# multi-pcb-analog-with-cc.net
KiCad netlist of a schematic drawn in EAGLE
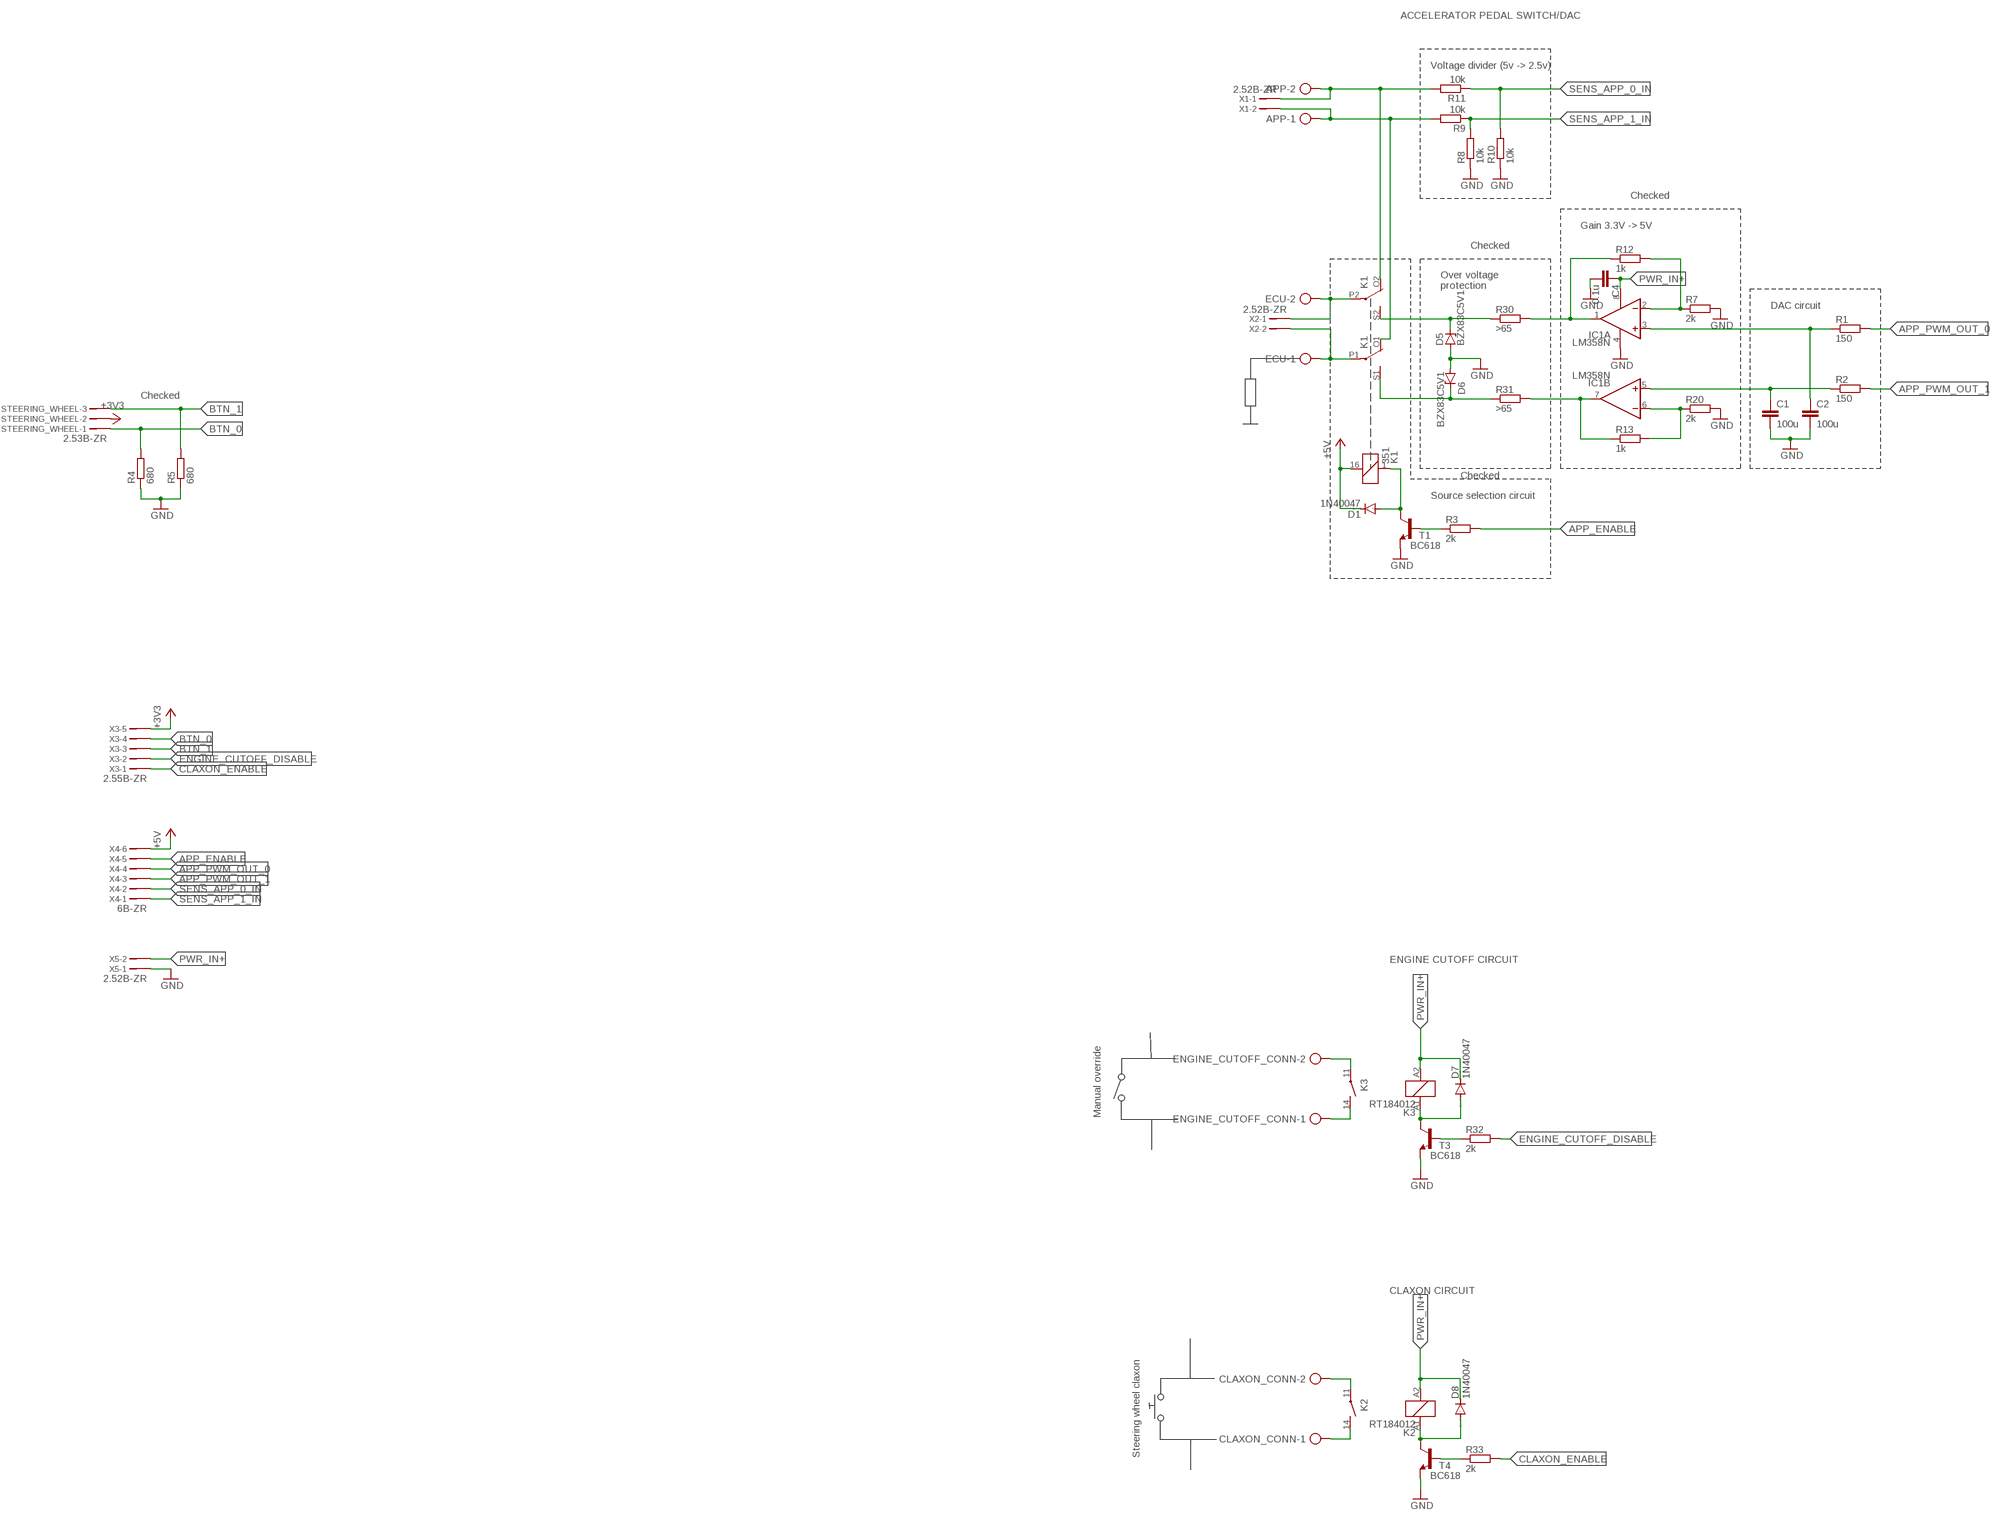
[diagram p0: schematic, sheet 1]

(export (version "E")
  (design (tool "Eeschema 10.0.6"))
  (components
    (comp (ref "APP")
      (value "AK300/2")
      (footprint "eagle-import:AK300_2")
      (libsource (lib "eagle-import") (part "AK300/2"))
    )
    (comp (ref "C1")
      (value "100u")
      (footprint "eagle-import:C025-050X050")
      (libsource (lib "eagle-import") (part "C-EU025-050X050"))
    )
    (comp (ref "C2")
      (value "100u")
      (footprint "eagle-import:C025-050X050")
      (libsource (lib "eagle-import") (part "C-EU025-050X050"))
    )
    (comp (ref "C4")
      (value "0.1u")
      (footprint "eagle-import:C025-050X050")
      (libsource (lib "eagle-import") (part "C-EU025-050X050"))
    )
    (comp (ref "CLAXON_CONN")
      (value "AK300/2")
      (footprint "eagle-import:AK300_2")
      (libsource (lib "eagle-import") (part "AK300/2"))
    )
    (comp (ref "D1")
      (value "1N40047")
      (footprint "eagle-import:DO41-7.6")
      (libsource (lib "eagle-import") (part "1N40047"))
    )
    (comp (ref "D5")
      (value "BZX83C5V1")
      (footprint "eagle-import:DO41Z7.6")
      (libsource (lib "eagle-import") (part "BZX857"))
    )
    (comp (ref "D6")
      (value "BZX83C5V1")
      (footprint "eagle-import:DO41Z7.6")
      (libsource (lib "eagle-import") (part "BZX857"))
    )
    (comp (ref "D7")
      (value "1N40047")
      (footprint "eagle-import:DO41-7.6")
      (libsource (lib "eagle-import") (part "1N40047"))
    )
    (comp (ref "D8")
      (value "1N40047")
      (footprint "eagle-import:DO41-7.6")
      (libsource (lib "eagle-import") (part "1N40047"))
    )
    (comp (ref "ECU")
      (value "AK300/2")
      (footprint "eagle-import:AK300_2")
      (libsource (lib "eagle-import") (part "AK300/2"))
    )
    (comp (ref "ENGINE_CUTOFF_CONN")
      (value "AK300/2")
      (footprint "eagle-import:AK300_2")
      (libsource (lib "eagle-import") (part "AK300/2"))
    )
    (comp (ref "IC1")
      (value "LM358N")
      (footprint "eagle-import:DIL08")
      (libsource (lib "eagle-import") (part "LM358N"))
    )
    (comp (ref "K1")
      (value "351")
      (footprint "eagle-import:351")
      (libsource (lib "eagle-import") (part "351"))
    )
    (comp (ref "K2")
      (value "RT184012")
      (footprint "eagle-import:RT-N_O12A3.5")
      (fields (field (name "MF") "TYCO ELECTRONICS"))
      (libsource (lib "eagle-import") (part "RT?184012"))
    )
    (comp (ref "K3")
      (value "RT184012")
      (footprint "eagle-import:RT-N_O12A3.5")
      (fields (field (name "MF") "TYCO ELECTRONICS"))
      (libsource (lib "eagle-import") (part "RT?184012"))
    )
    (comp (ref "R1")
      (value "150")
      (footprint "eagle-import:0207_7")
      (libsource (lib "eagle-import") (part "R-EU_0207/7"))
    )
    (comp (ref "R2")
      (value "150")
      (footprint "eagle-import:0207_7")
      (libsource (lib "eagle-import") (part "R-EU_0207/7"))
    )
    (comp (ref "R3")
      (value "2k")
      (footprint "eagle-import:0207_7")
      (libsource (lib "eagle-import") (part "R-EU_0207/7"))
    )
    (comp (ref "R4")
      (value "680")
      (footprint "eagle-import:0207_7")
      (libsource (lib "eagle-import") (part "R-EU_0207/7"))
    )
    (comp (ref "R5")
      (value "680")
      (footprint "eagle-import:0207_7")
      (libsource (lib "eagle-import") (part "R-EU_0207/7"))
    )
    (comp (ref "R7")
      (value "2k")
      (footprint "eagle-import:0207_7")
      (libsource (lib "eagle-import") (part "R-EU_0207/7"))
    )
    (comp (ref "R8")
      (value "10k")
      (footprint "eagle-import:0207_7")
      (libsource (lib "eagle-import") (part "R-EU_0207/7"))
    )
    (comp (ref "R9")
      (value "10k")
      (footprint "eagle-import:0207_7")
      (libsource (lib "eagle-import") (part "R-EU_0207/7"))
    )
    (comp (ref "R10")
      (value "10k")
      (footprint "eagle-import:0207_7")
      (libsource (lib "eagle-import") (part "R-EU_0207/7"))
    )
    (comp (ref "R11")
      (value "10k")
      (footprint "eagle-import:0207_7")
      (libsource (lib "eagle-import") (part "R-EU_0207/7"))
    )
    (comp (ref "R12")
      (value "1k")
      (footprint "eagle-import:0207_7")
      (libsource (lib "eagle-import") (part "R-EU_0207/7"))
    )
    (comp (ref "R13")
      (value "1k")
      (footprint "eagle-import:0207_7")
      (libsource (lib "eagle-import") (part "R-EU_0207/7"))
    )
    (comp (ref "R20")
      (value "2k")
      (footprint "eagle-import:0207_7")
      (libsource (lib "eagle-import") (part "R-EU_0207/7"))
    )
    (comp (ref "R30")
      (value ">65")
      (footprint "eagle-import:0207_7")
      (libsource (lib "eagle-import") (part "R-EU_0207/7"))
    )
    (comp (ref "R31")
      (value ">65")
      (footprint "eagle-import:0207_7")
      (libsource (lib "eagle-import") (part "R-EU_0207/7"))
    )
    (comp (ref "R32")
      (value "2k")
      (footprint "eagle-import:0207_7")
      (libsource (lib "eagle-import") (part "R-EU_0207/7"))
    )
    (comp (ref "R33")
      (value "2k")
      (footprint "eagle-import:0207_7")
      (libsource (lib "eagle-import") (part "R-EU_0207/7"))
    )
    (comp (ref "STEERING_WHEEL")
      (value "2.53B-ZR")
      (footprint "eagle-import:B3B-ZR2.5")
      (libsource (lib "eagle-import") (part "?3B-ZR2.5"))
    )
    (comp (ref "T1")
      (value "BC618")
      (footprint "eagle-import:TO92-EBC")
      (libsource (lib "eagle-import") (part "BC618"))
    )
    (comp (ref "T3")
      (value "BC618")
      (footprint "eagle-import:TO92-EBC")
      (libsource (lib "eagle-import") (part "BC618"))
    )
    (comp (ref "T4")
      (value "BC618")
      (footprint "eagle-import:TO92-EBC")
      (libsource (lib "eagle-import") (part "BC618"))
    )
    (comp (ref "X1")
      (value "2.52B-ZR")
      (footprint "eagle-import:B2B-ZR2.5")
      (libsource (lib "eagle-import") (part "?2B-ZR2.5"))
    )
    (comp (ref "X2")
      (value "2.52B-ZR")
      (footprint "eagle-import:B2B-ZR2.5")
      (libsource (lib "eagle-import") (part "?2B-ZR2.5"))
    )
    (comp (ref "X3")
      (value "2.55B-ZR")
      (footprint "eagle-import:B5B-ZR2.5")
      (libsource (lib "eagle-import") (part "?5B-ZR2.5"))
    )
    (comp (ref "X4")
      (value "6B-ZR")
      (footprint "eagle-import:B6B-ZR2.5")
      (libsource (lib "eagle-import") (part "?6B-ZR"))
    )
    (comp (ref "X5")
      (value "2.52B-ZR")
      (footprint "eagle-import:B2B-ZR2.5")
      (libsource (lib "eagle-import") (part "?2B-ZR2.5"))
    )
  )
  (nets
    (net (code "1") (name "+3V3") (class "Default")
      (node (ref "STEERING_WHEEL") (pin "2") (pinfunction "1_2") (pintype "passive"))
      (node (ref "X3") (pin "5") (pinfunction "1_5") (pintype "passive"))
    )
    (net (code "2") (name "+5V") (class "Default")
      (node (ref "D1") (pin "C") (pinfunction "C_C") (pintype "passive"))
      (node (ref "K1") (pin "16") (pinfunction "2_16") (pintype "passive"))
      (node (ref "X4") (pin "6") (pinfunction "1_6") (pintype "passive"))
    )
    (net (code "3") (name "APP_ENABLE") (class "Default")
      (node (ref "R3") (pin "2") (pinfunction "2_2") (pintype "passive"))
      (node (ref "X4") (pin "5") (pinfunction "1_5") (pintype "passive"))
    )
    (net (code "4") (name "APP_PWM_OUT_0") (class "Default")
      (node (ref "R1") (pin "2") (pinfunction "2_2") (pintype "passive"))
      (node (ref "X4") (pin "4") (pinfunction "1_4") (pintype "passive"))
    )
    (net (code "5") (name "APP_PWM_OUT_1") (class "Default")
      (node (ref "R2") (pin "2") (pinfunction "2_2") (pintype "passive"))
      (node (ref "X4") (pin "3") (pinfunction "1_3") (pintype "passive"))
    )
    (net (code "6") (name "BTN_0") (class "Default")
      (node (ref "R4") (pin "2") (pinfunction "2_2") (pintype "passive"))
      (node (ref "STEERING_WHEEL") (pin "1") (pinfunction "1_1") (pintype "passive"))
      (node (ref "X3") (pin "4") (pinfunction "1_4") (pintype "passive"))
    )
    (net (code "7") (name "BTN_1") (class "Default")
      (node (ref "R5") (pin "2") (pinfunction "2_2") (pintype "passive"))
      (node (ref "STEERING_WHEEL") (pin "3") (pinfunction "1_3") (pintype "passive"))
      (node (ref "X3") (pin "3") (pinfunction "1_3") (pintype "passive"))
    )
    (net (code "8") (name "CLAXON_ENABLE") (class "Default")
      (node (ref "R33") (pin "2") (pinfunction "2_2") (pintype "passive"))
      (node (ref "X3") (pin "1") (pinfunction "1_1") (pintype "passive"))
    )
    (net (code "9") (name "ENGINE_CUTOFF_DISABLE") (class "Default")
      (node (ref "R32") (pin "2") (pinfunction "2_2") (pintype "passive"))
      (node (ref "X3") (pin "2") (pinfunction "1_2") (pintype "passive"))
    )
    (net (code "10") (name "GND") (class "Default")
      (node (ref "C1") (pin "2") (pinfunction "2_2") (pintype "passive"))
      (node (ref "C2") (pin "2") (pinfunction "2_2") (pintype "passive"))
      (node (ref "C4") (pin "2") (pinfunction "2_2") (pintype "passive"))
      (node (ref "D5") (pin "A") (pinfunction "A_A") (pintype "passive"))
      (node (ref "D6") (pin "A") (pinfunction "A_A") (pintype "passive"))
      (node (ref "IC1") (pin "4") (pinfunction "V-_4") (pintype "power_in"))
      (node (ref "R10") (pin "1") (pinfunction "1_1") (pintype "passive"))
      (node (ref "R20") (pin "2") (pinfunction "2_2") (pintype "passive"))
      (node (ref "R4") (pin "1") (pinfunction "1_1") (pintype "passive"))
      (node (ref "R5") (pin "1") (pinfunction "1_1") (pintype "passive"))
      (node (ref "R7") (pin "2") (pinfunction "2_2") (pintype "passive"))
      (node (ref "R8") (pin "1") (pinfunction "1_1") (pintype "passive"))
      (node (ref "T1") (pin "E") (pinfunction "E_E") (pintype "passive"))
      (node (ref "T3") (pin "E") (pinfunction "E_E") (pintype "passive"))
      (node (ref "T4") (pin "E") (pinfunction "E_E") (pintype "passive"))
      (node (ref "X5") (pin "1") (pinfunction "1_1") (pintype "passive"))
    )
    (net (code "11") (name "Net-(APPA-KL)") (class "Default")
      (node (ref "APP") (pin "1") (pinfunction "KL_1") (pintype "passive"))
      (node (ref "K1") (pin "O1") (pinfunction "O_O1") (pintype "passive"))
      (node (ref "R9") (pin "2") (pinfunction "2_2") (pintype "passive"))
      (node (ref "X1") (pin "2") (pinfunction "1_2") (pintype "passive"))
    )
    (net (code "12") (name "Net-(APPB-KL)") (class "Default")
      (node (ref "APP") (pin "2") (pinfunction "KL_2") (pintype "passive"))
      (node (ref "K1") (pin "O2") (pinfunction "O_O2") (pintype "passive"))
      (node (ref "R11") (pin "2") (pinfunction "2_2") (pintype "passive"))
      (node (ref "X1") (pin "1") (pinfunction "1_1") (pintype "passive"))
    )
    (net (code "13") (name "Net-(CLAXON_CONNA-KL)") (class "Default")
      (node (ref "CLAXON_CONN") (pin "1") (pinfunction "KL_1") (pintype "passive"))
      (node (ref "K2") (pin "14") (pinfunction "S_14") (pintype "passive"))
    )
    (net (code "14") (name "Net-(CLAXON_CONNB-KL)") (class "Default")
      (node (ref "CLAXON_CONN") (pin "2") (pinfunction "KL_2") (pintype "passive"))
      (node (ref "K2") (pin "11") (pinfunction "P_11") (pintype "passive"))
    )
    (net (code "15") (name "Net-(D1-PadA)") (class "Default")
      (node (ref "D1") (pin "A") (pinfunction "A_A") (pintype "passive"))
      (node (ref "K1") (pin "1") (pinfunction "1_1") (pintype "passive"))
      (node (ref "T1") (pin "C") (pinfunction "C_C") (pintype "passive"))
    )
    (net (code "16") (name "Net-(ECUA-KL)") (class "Default")
      (node (ref "ECU") (pin "1") (pinfunction "KL_1") (pintype "passive"))
      (node (ref "K1") (pin "P1") (pinfunction "P_P1") (pintype "passive"))
      (node (ref "X2") (pin "2") (pinfunction "1_2") (pintype "passive"))
    )
    (net (code "17") (name "Net-(ECUB-KL)") (class "Default")
      (node (ref "ECU") (pin "2") (pinfunction "KL_2") (pintype "passive"))
      (node (ref "K1") (pin "P2") (pinfunction "P_P2") (pintype "passive"))
      (node (ref "X2") (pin "1") (pinfunction "1_1") (pintype "passive"))
    )
    (net (code "18") (name "Net-(ENGINE_CUTOFF_CONNA-KL)") (class "Default")
      (node (ref "ENGINE_CUTOFF_CONN") (pin "1") (pinfunction "KL_1") (pintype "passive"))
      (node (ref "K3") (pin "14") (pinfunction "S_14") (pintype "passive"))
    )
    (net (code "19") (name "Net-(ENGINE_CUTOFF_CONNB-KL)") (class "Default")
      (node (ref "ENGINE_CUTOFF_CONN") (pin "2") (pinfunction "KL_2") (pintype "passive"))
      (node (ref "K3") (pin "11") (pinfunction "P_11") (pintype "passive"))
    )
    (net (code "20") (name "Net-(IC1A-+IN)") (class "Default")
      (node (ref "C2") (pin "1") (pinfunction "1_1") (pintype "passive"))
      (node (ref "IC1") (pin "3") (pinfunction "+IN_3") (pintype "input"))
      (node (ref "R1") (pin "1") (pinfunction "1_1") (pintype "passive"))
    )
    (net (code "21") (name "Net-(IC1A--IN)") (class "Default")
      (node (ref "IC1") (pin "2") (pinfunction "-IN_2") (pintype "input"))
      (node (ref "R12") (pin "2") (pinfunction "2_2") (pintype "passive"))
      (node (ref "R7") (pin "1") (pinfunction "1_1") (pintype "passive"))
    )
    (net (code "22") (name "Net-(IC1A-OUT)") (class "Default")
      (node (ref "IC1") (pin "1") (pinfunction "OUT_1") (pintype "output"))
      (node (ref "R12") (pin "1") (pinfunction "1_1") (pintype "passive"))
      (node (ref "R30") (pin "2") (pinfunction "2_2") (pintype "passive"))
    )
    (net (code "23") (name "Net-(IC1B-+IN)") (class "Default")
      (node (ref "C1") (pin "1") (pinfunction "1_1") (pintype "passive"))
      (node (ref "IC1") (pin "5") (pinfunction "+IN_5") (pintype "input"))
      (node (ref "R2") (pin "1") (pinfunction "1_1") (pintype "passive"))
    )
    (net (code "24") (name "Net-(IC1B--IN)") (class "Default")
      (node (ref "IC1") (pin "6") (pinfunction "-IN_6") (pintype "input"))
      (node (ref "R13") (pin "2") (pinfunction "2_2") (pintype "passive"))
      (node (ref "R20") (pin "1") (pinfunction "1_1") (pintype "passive"))
    )
    (net (code "25") (name "Net-(IC1B-OUT)") (class "Default")
      (node (ref "IC1") (pin "7") (pinfunction "OUT_7") (pintype "output"))
      (node (ref "R13") (pin "1") (pinfunction "1_1") (pintype "passive"))
      (node (ref "R31") (pin "2") (pinfunction "2_2") (pintype "passive"))
    )
    (net (code "26") (name "Net-(K1B-S)") (class "Default")
      (node (ref "D6") (pin "C") (pinfunction "C_C") (pintype "passive"))
      (node (ref "K1") (pin "S1") (pinfunction "S_S1") (pintype "passive"))
      (node (ref "R31") (pin "1") (pinfunction "1_1") (pintype "passive"))
    )
    (net (code "27") (name "Net-(K1C-S)") (class "Default")
      (node (ref "D5") (pin "C") (pinfunction "C_C") (pintype "passive"))
      (node (ref "K1") (pin "S2") (pinfunction "S_S2") (pintype "passive"))
      (node (ref "R30") (pin "1") (pinfunction "1_1") (pintype "passive"))
    )
    (net (code "28") (name "Net-(K2A-1)") (class "Default")
      (node (ref "D8") (pin "A") (pinfunction "A_A") (pintype "passive"))
      (node (ref "K2") (pin "A1") (pinfunction "1_A1") (pintype "passive"))
      (node (ref "T4") (pin "C") (pinfunction "C_C") (pintype "passive"))
    )
    (net (code "29") (name "Net-(K3A-1)") (class "Default")
      (node (ref "D7") (pin "A") (pinfunction "A_A") (pintype "passive"))
      (node (ref "K3") (pin "A1") (pinfunction "1_A1") (pintype "passive"))
      (node (ref "T3") (pin "C") (pinfunction "C_C") (pintype "passive"))
    )
    (net (code "30") (name "Net-(R3-Pad1)") (class "Default")
      (node (ref "R3") (pin "1") (pinfunction "1_1") (pintype "passive"))
      (node (ref "T1") (pin "B") (pinfunction "B_B") (pintype "passive"))
    )
    (net (code "31") (name "Net-(R32-Pad1)") (class "Default")
      (node (ref "R32") (pin "1") (pinfunction "1_1") (pintype "passive"))
      (node (ref "T3") (pin "B") (pinfunction "B_B") (pintype "passive"))
    )
    (net (code "32") (name "Net-(R33-Pad1)") (class "Default")
      (node (ref "R33") (pin "1") (pinfunction "1_1") (pintype "passive"))
      (node (ref "T4") (pin "B") (pinfunction "B_B") (pintype "passive"))
    )
    (net (code "33") (name "PWR_IN+") (class "Default")
      (node (ref "C4") (pin "1") (pinfunction "1_1") (pintype "passive"))
      (node (ref "D7") (pin "C") (pinfunction "C_C") (pintype "passive"))
      (node (ref "D8") (pin "C") (pinfunction "C_C") (pintype "passive"))
      (node (ref "IC1") (pin "8") (pinfunction "V+_8") (pintype "power_in"))
      (node (ref "K2") (pin "A2") (pinfunction "2_A2") (pintype "passive"))
      (node (ref "K3") (pin "A2") (pinfunction "2_A2") (pintype "passive"))
      (node (ref "X5") (pin "2") (pinfunction "1_2") (pintype "passive"))
    )
    (net (code "34") (name "SENS_APP_0_IN") (class "Default")
      (node (ref "R10") (pin "2") (pinfunction "2_2") (pintype "passive"))
      (node (ref "R11") (pin "1") (pinfunction "1_1") (pintype "passive"))
      (node (ref "X4") (pin "2") (pinfunction "1_2") (pintype "passive"))
    )
    (net (code "35") (name "SENS_APP_1_IN") (class "Default")
      (node (ref "R8") (pin "2") (pinfunction "2_2") (pintype "passive"))
      (node (ref "R9") (pin "1") (pinfunction "1_1") (pintype "passive"))
      (node (ref "X4") (pin "1") (pinfunction "1_1") (pintype "passive"))
    )
  )
)
